# USB.net
KiCad netlist of a schematic drawn in Altium Designer
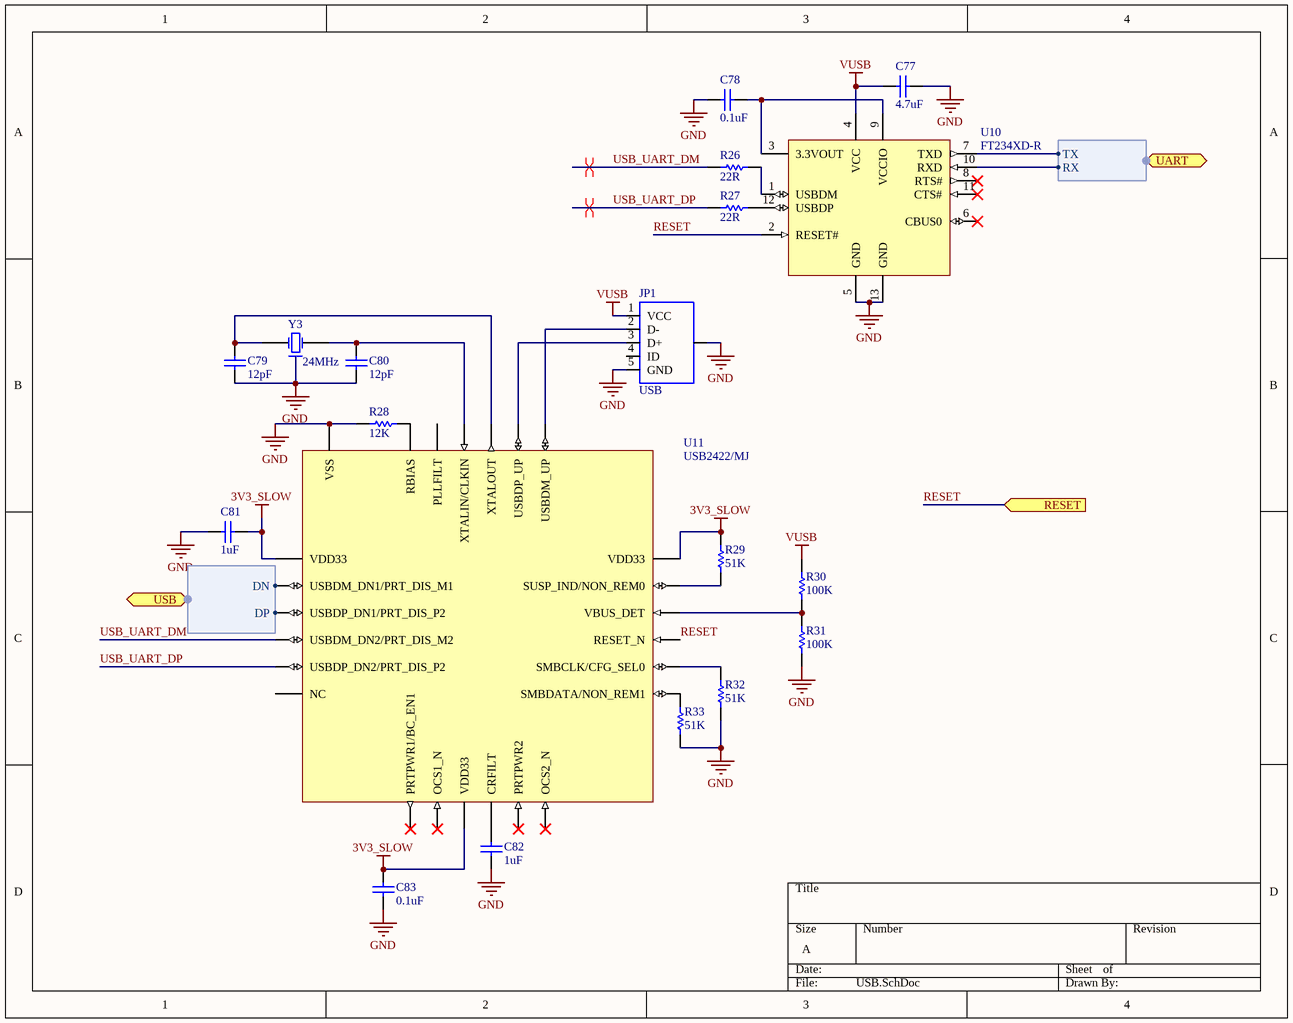
[diagram p0: USB.SchDoc]

(export (version "E")
  (design (tool "Eeschema 10.0.6"))
  (components
    (comp (ref "C77")
      (value "4.7uF")
      (footprint "C0402[1005X55]")
      (description "4.7uF 6.3V 20% 0402 (1005 Metric)")
      (fields (field (name "PARTNUMBER") "GRM155R60J475ME47D") (field (name "MANUFACTURER") "Murata"))
      (libsource (lib "Capacitors") (part "CAP_4.7uF_6.3V_0402_20%"))
    )
    (comp (ref "C78")
      (value "0.1uF")
      (footprint "C0402[1005X55]")
      (description "0.1uF 6.3V 10% 0402 (1005 Metric)")
      (fields (field (name "PARTNUMBER") "GRM155R70J104KA01D") (field (name "MANUFACTURER") "Murata"))
      (libsource (lib "Capacitors") (part "CAP_0.1uF_6.3V_0402_10%"))
    )
    (comp (ref "C79")
      (value "12pF")
      (footprint "C0402[1005X55]")
      (description "12pF 50V 5% 0402 (1005 Metric)")
      (fields (field (name "PARTNUMBER") "GRM1555C1H120JA01D") (field (name "MANUFACTURER") "Murata"))
      (libsource (lib "Capacitors") (part "CAP_12pF_50V_0402_5%"))
    )
    (comp (ref "C80")
      (value "12pF")
      (footprint "C0402[1005X55]")
      (description "12pF 50V 5% 0402 (1005 Metric)")
      (fields (field (name "PARTNUMBER") "GRM1555C1H120JA01D") (field (name "MANUFACTURER") "Murata"))
      (libsource (lib "Capacitors") (part "CAP_12pF_50V_0402_5%"))
    )
    (comp (ref "C81")
      (value "1uF")
      (footprint "C0402[1005X55]")
      (description "1uF 6.3V 10% 0402 (1005 Metric)")
      (fields (field (name "PARTNUMBER") "GRM155R70J105KA12D") (field (name "MANUFACTURER") "Murata"))
      (libsource (lib "Capacitors") (part "CAP_1uF_6.3V_0402_10%"))
    )
    (comp (ref "C82")
      (value "1uF")
      (footprint "C0402[1005X55]")
      (description "1uF 6.3V 10% 0402 (1005 Metric)")
      (fields (field (name "PARTNUMBER") "GRM155R70J105KA12D") (field (name "MANUFACTURER") "Murata"))
      (libsource (lib "Capacitors") (part "CAP_1uF_6.3V_0402_10%"))
    )
    (comp (ref "C83")
      (value "0.1uF")
      (footprint "C0402[1005X55]")
      (description "0.1uF 6.3V 10% 0402 (1005 Metric)")
      (fields (field (name "PARTNUMBER") "GRM155R70J104KA01D") (field (name "MANUFACTURER") "Murata"))
      (libsource (lib "Capacitors") (part "CAP_0.1uF_6.3V_0402_10%"))
    )
    (comp (ref "JP1")
      (value "USB")
      (footprint "USB-MICROB")
      (fields (field (name "PARTNUMBER") "10118192-0001LF") (field (name "MANUFACTURER") "Amphenol FCI"))
      (libsource (lib "Connectors") (part "USB_MICROB_SMT"))
    )
    (comp (ref "R26")
      (value "22R")
      (footprint "R0402[1005]")
      (description "22R 0.063W 1% 0402 (1005 Metric)")
      (fields (field (name "MANUFACTURER") "KOA Speer") (field (name "PARTNUMBER") "RK73H1ETTP22R0F"))
      (libsource (lib "Resistors") (part "RES_22R_0402_1%"))
    )
    (comp (ref "R27")
      (value "22R")
      (footprint "R0402[1005]")
      (description "22R 0.063W 1% 0402 (1005 Metric)")
      (fields (field (name "MANUFACTURER") "KOA Speer") (field (name "PARTNUMBER") "RK73H1ETTP22R0F"))
      (libsource (lib "Resistors") (part "RES_22R_0402_1%"))
    )
    (comp (ref "R28")
      (value "12K")
      (footprint "R0402[1005]")
      (description "12K 0.063W 1% 0402 (1005 Metric)")
      (fields (field (name "MANUFACTURER") "KOA Speer") (field (name "PARTNUMBER") "RK73H1ETTP1202F"))
      (libsource (lib "Resistors") (part "RES_12K_0402_1%"))
    )
    (comp (ref "R29")
      (value "51K")
      (footprint "R0402[1005]")
      (description "51K 0.063W 1% 0402 (1005 Metric)")
      (fields (field (name "MANUFACTURER") "KOA Speer") (field (name "PARTNUMBER") "RK73H1ETTP5102F"))
      (libsource (lib "Resistors") (part "RES_51K_0402_1%"))
    )
    (comp (ref "R30")
      (value "100K")
      (footprint "R0402[1005]")
      (description "100K 0.063W 1% 0402 (1005 Metric)")
      (fields (field (name "MANUFACTURER") "KOA Speer") (field (name "PARTNUMBER") "RK73H1ETTP1003F"))
      (libsource (lib "Resistors") (part "RES_100K_0402_1%"))
    )
    (comp (ref "R31")
      (value "100K")
      (footprint "R0402[1005]")
      (description "100K 0.063W 1% 0402 (1005 Metric)")
      (fields (field (name "MANUFACTURER") "KOA Speer") (field (name "PARTNUMBER") "RK73H1ETTP1003F"))
      (libsource (lib "Resistors") (part "RES_100K_0402_1%"))
    )
    (comp (ref "R32")
      (value "51K")
      (footprint "R0402[1005]")
      (description "51K 0.063W 1% 0402 (1005 Metric)")
      (fields (field (name "MANUFACTURER") "KOA Speer") (field (name "PARTNUMBER") "RK73H1ETTP5102F"))
      (libsource (lib "Resistors") (part "RES_51K_0402_1%"))
    )
    (comp (ref "R33")
      (value "51K")
      (footprint "R0402[1005]")
      (description "51K 0.063W 1% 0402 (1005 Metric)")
      (fields (field (name "MANUFACTURER") "KOA Speer") (field (name "PARTNUMBER") "RK73H1ETTP5102F"))
      (libsource (lib "Resistors") (part "RES_51K_0402_1%"))
    )
    (comp (ref "U10")
      (value "FT234XD-R")
      (footprint "DFN-12_V")
      (description "FT234XD USB to BASIC UART IC, -40 to +85 degC, 12-Pin DFN, Pb-Free, Tape and Reel")
      (fields (field (name "MANUFACTURER") "FTDI"))
      (libsource (lib "Altium Content Vault") (part "FTDI-FT234XD-DFN-12"))
    )
    (comp (ref "U11")
      (value "USB2422/MJ")
      (footprint "QFN-24 (4x4MM)")
      (description "USB Hub IC 2-Port")
      (fields (field (name "MANUFACTURER") "Microchip"))
      (libsource (lib "ICs-USBInterface") (part "USB2422/MJ"))
    )
    (comp (ref "Y3")
      (value "24MHz")
      (footprint "CRYSTAL_2.0x1.6")
      (fields (field (name "PARTNUMBER") "FA-128 24.0000MF10Z-W3") (field (name "MANUFACTURER") "EPSON"))
      (libsource (lib "Components") (part "FA-128 24.0000MF10Z-W3"))
    )
  )
  (nets
    (net (code "3") (name "/DN") (class "Default")
      (node (ref "U11") (pin "2") (pinfunction "USBDM_DN1/PRT_DIS_M1_2") (pintype "bidirectional"))
    )
    (net (code "4") (name "/DP") (class "Default")
      (node (ref "U11") (pin "3") (pinfunction "USBDP_DN1/PRT_DIS_P2_3") (pintype "bidirectional"))
    )
    (net (code "5") (name "/RESET") (class "Default")
      (node (ref "U10") (pin "2") (pinfunction "RESET#_2") (pintype "input"))
      (node (ref "U11") (pin "15") (pinfunction "RESET_N_15") (pintype "input"))
    )
    (net (code "6") (name "/RX") (class "Default")
      (node (ref "U10") (pin "10") (pinfunction "RXD_10") (pintype "input"))
    )
    (net (code "7") (name "/TX") (class "Default")
      (node (ref "U10") (pin "7") (pinfunction "TXD_7") (pintype "output"))
    )
    (net (code "8") (name "/USB_UART_DM") (class "Default")
      (node (ref "R26") (pin "1") (pinfunction "1_1") (pintype "passive"))
      (node (ref "U11") (pin "4") (pinfunction "USBDM_DN2/PRT_DIS_M2_4") (pintype "bidirectional"))
    )
    (net (code "9") (name "/USB_UART_DP") (class "Default")
      (node (ref "R27") (pin "1") (pinfunction "1_1") (pintype "passive"))
      (node (ref "U11") (pin "5") (pinfunction "USBDP_DN2/PRT_DIS_P2_5") (pintype "bidirectional"))
    )
    (net (code "12") (name "3V3_SLOW") (class "Default")
      (node (ref "C81") (pin "2") (pinfunction "2_2") (pintype "passive"))
      (node (ref "C83") (pin "2") (pinfunction "2_2") (pintype "passive"))
      (node (ref "R29") (pin "2") (pinfunction "2_2") (pintype "passive"))
      (node (ref "U11") (pin "1") (pinfunction "VDD33_1") (pintype "power_in"))
      (node (ref "U11") (pin "18") (pinfunction "VDD33_18") (pintype "power_in"))
      (node (ref "U11") (pin "9") (pinfunction "VDD33_9") (pintype "power_in"))
    )
    (net (code "13") (name "GND") (class "Default")
      (node (ref "C77") (pin "2") (pinfunction "2_2") (pintype "passive"))
      (node (ref "C78") (pin "2") (pinfunction "2_2") (pintype "passive"))
      (node (ref "C79") (pin "1") (pinfunction "1_1") (pintype "passive"))
      (node (ref "C80") (pin "1") (pinfunction "1_1") (pintype "passive"))
      (node (ref "C81") (pin "1") (pinfunction "1_1") (pintype "passive"))
      (node (ref "C82") (pin "1") (pinfunction "1_1") (pintype "passive"))
      (node (ref "C83") (pin "1") (pinfunction "1_1") (pintype "passive"))
      (node (ref "JP1") (pin "5") (pinfunction "GND_5") (pintype "passive"))
      (node (ref "JP1") (pin "6") (pinfunction "SHIELD_6") (pintype "passive"))
      (node (ref "R28") (pin "1") (pinfunction "1_1") (pintype "passive"))
      (node (ref "R31") (pin "1") (pinfunction "1_1") (pintype "passive"))
      (node (ref "R32") (pin "1") (pinfunction "1_1") (pintype "passive"))
      (node (ref "R33") (pin "1") (pinfunction "1_1") (pintype "passive"))
      (node (ref "U10") (pin "13") (pinfunction "GND_13") (pintype "power_in"))
      (node (ref "U10") (pin "5") (pinfunction "GND_5") (pintype "power_in"))
      (node (ref "U11") (pin "25") (pinfunction "VSS_25") (pintype "power_in"))
      (node (ref "Y3") (pin "2") (pinfunction "2_2") (pintype "passive"))
    )
    (net (code "14") (name "Net-(JP1-D+)") (class "Default")
      (node (ref "JP1") (pin "3") (pinfunction "D+_3") (pintype "passive"))
      (node (ref "U11") (pin "20") (pinfunction "USBDP_UP_20") (pintype "bidirectional"))
    )
    (net (code "15") (name "Net-(JP1-D-)") (class "Default")
      (node (ref "JP1") (pin "2") (pinfunction "D-_2") (pintype "passive"))
      (node (ref "U11") (pin "19") (pinfunction "USBDM_UP_19") (pintype "bidirectional"))
    )
    (net (code "16") (name "Net-(U10-3.3VOUT)") (class "Default")
      (node (ref "C78") (pin "1") (pinfunction "1_1") (pintype "passive"))
      (node (ref "U10") (pin "3") (pinfunction "3.3VOUT_3") (pintype "power_in"))
      (node (ref "U10") (pin "9") (pinfunction "VCCIO_9") (pintype "power_in"))
    )
    (net (code "17") (name "Net-(U10-USBDM)") (class "Default")
      (node (ref "R26") (pin "2") (pinfunction "2_2") (pintype "passive"))
      (node (ref "U10") (pin "1") (pinfunction "USBDM_1") (pintype "bidirectional"))
    )
    (net (code "18") (name "Net-(U10-USBDP)") (class "Default")
      (node (ref "R27") (pin "2") (pinfunction "2_2") (pintype "passive"))
      (node (ref "U10") (pin "12") (pinfunction "USBDP_12") (pintype "bidirectional"))
    )
    (net (code "19") (name "Net-(U11-CRFILT)") (class "Default")
      (node (ref "C82") (pin "2") (pinfunction "2_2") (pintype "passive"))
      (node (ref "U11") (pin "10") (pinfunction "CRFILT_10") (pintype "passive"))
    )
    (net (code "20") (name "Net-(U11-RBIAS)") (class "Default")
      (node (ref "R28") (pin "2") (pinfunction "2_2") (pintype "passive"))
      (node (ref "U11") (pin "24") (pinfunction "RBIAS_24") (pintype "passive"))
    )
    (net (code "21") (name "Net-(U11-SMBCLK{slash}CFG_SEL0)") (class "Default")
      (node (ref "R32") (pin "2") (pinfunction "2_2") (pintype "passive"))
      (node (ref "U11") (pin "14") (pinfunction "SMBCLK/CFG_SEL0_14") (pintype "bidirectional"))
    )
    (net (code "22") (name "Net-(U11-SMBDATA{slash}NON_REM1)") (class "Default")
      (node (ref "R33") (pin "2") (pinfunction "2_2") (pintype "passive"))
      (node (ref "U11") (pin "13") (pinfunction "SMBDATA/NON_REM1_13") (pintype "bidirectional"))
    )
    (net (code "23") (name "Net-(U11-SUSP_IND{slash}NON_REM0)") (class "Default")
      (node (ref "R29") (pin "1") (pinfunction "1_1") (pintype "passive"))
      (node (ref "U11") (pin "17") (pinfunction "SUSP_IND/NON_REM0_17") (pintype "bidirectional"))
    )
    (net (code "24") (name "Net-(U11-VBUS_DET)") (class "Default")
      (node (ref "R30") (pin "1") (pinfunction "1_1") (pintype "passive"))
      (node (ref "R31") (pin "2") (pinfunction "2_2") (pintype "passive"))
      (node (ref "U11") (pin "16") (pinfunction "VBUS_DET_16") (pintype "input"))
    )
    (net (code "25") (name "Net-(U11-XTALIN{slash}CLKIN)") (class "Default")
      (node (ref "C80") (pin "2") (pinfunction "2_2") (pintype "passive"))
      (node (ref "U11") (pin "22") (pinfunction "XTALIN/CLKIN_22") (pintype "input"))
      (node (ref "Y3") (pin "3") (pinfunction "X2_3") (pintype "passive"))
    )
    (net (code "26") (name "Net-(U11-XTALOUT)") (class "Default")
      (node (ref "C79") (pin "2") (pinfunction "2_2") (pintype "passive"))
      (node (ref "U11") (pin "21") (pinfunction "XTALOUT_21") (pintype "output"))
      (node (ref "Y3") (pin "1") (pinfunction "X1_1") (pintype "passive"))
    )
    (net (code "27") (name "VUSB") (class "Default")
      (node (ref "C77") (pin "1") (pinfunction "1_1") (pintype "passive"))
      (node (ref "JP1") (pin "1") (pinfunction "VCC_1") (pintype "passive"))
      (node (ref "R30") (pin "2") (pinfunction "2_2") (pintype "passive"))
      (node (ref "U10") (pin "4") (pinfunction "VCC_4") (pintype "power_in"))
    )
    (net (code "28") (name "unconnected-(JP1-ID-Pad4)") (class "Default")
      (node (ref "JP1") (pin "4") (pinfunction "ID_4") (pintype "passive"))
    )
    (net (code "29") (name "unconnected-(U10-CBUS0-Pad6)") (class "Default")
      (node (ref "U10") (pin "6") (pinfunction "CBUS0_6") (pintype "bidirectional+no_connect"))
    )
    (net (code "30") (name "unconnected-(U10-CTS#-Pad11)") (class "Default")
      (node (ref "U10") (pin "11") (pinfunction "CTS#_11") (pintype "input+no_connect"))
    )
    (net (code "31") (name "unconnected-(U10-RTS#-Pad8)") (class "Default")
      (node (ref "U10") (pin "8") (pinfunction "RTS#_8") (pintype "output+no_connect"))
    )
    (net (code "32") (name "unconnected-(U11-NC-Pad6)") (class "Default")
      (node (ref "U11") (pin "6") (pinfunction "NC_6") (pintype "passive"))
    )
    (net (code "33") (name "unconnected-(U11-OCS1_N-Pad8)") (class "Default")
      (node (ref "U11") (pin "8") (pinfunction "OCS1_N_8") (pintype "input+no_connect"))
    )
    (net (code "34") (name "unconnected-(U11-OCS2_N-Pad12)") (class "Default")
      (node (ref "U11") (pin "12") (pinfunction "OCS2_N_12") (pintype "input+no_connect"))
    )
    (net (code "35") (name "unconnected-(U11-PLLFILT-Pad23)") (class "Default")
      (node (ref "U11") (pin "23") (pinfunction "PLLFILT_23") (pintype "passive"))
    )
    (net (code "36") (name "unconnected-(U11-PRTPWR1{slash}BC_EN1-Pad7)") (class "Default")
      (node (ref "U11") (pin "7") (pinfunction "PRTPWR1/BC_EN1_7") (pintype "output+no_connect"))
    )
    (net (code "37") (name "unconnected-(U11-PRTPWR2-Pad11)") (class "Default")
      (node (ref "U11") (pin "11") (pinfunction "PRTPWR2_11") (pintype "input+no_connect"))
    )
  )
)
